# linearSensor.net
KiCad netlist of a schematic drawn in EAGLE
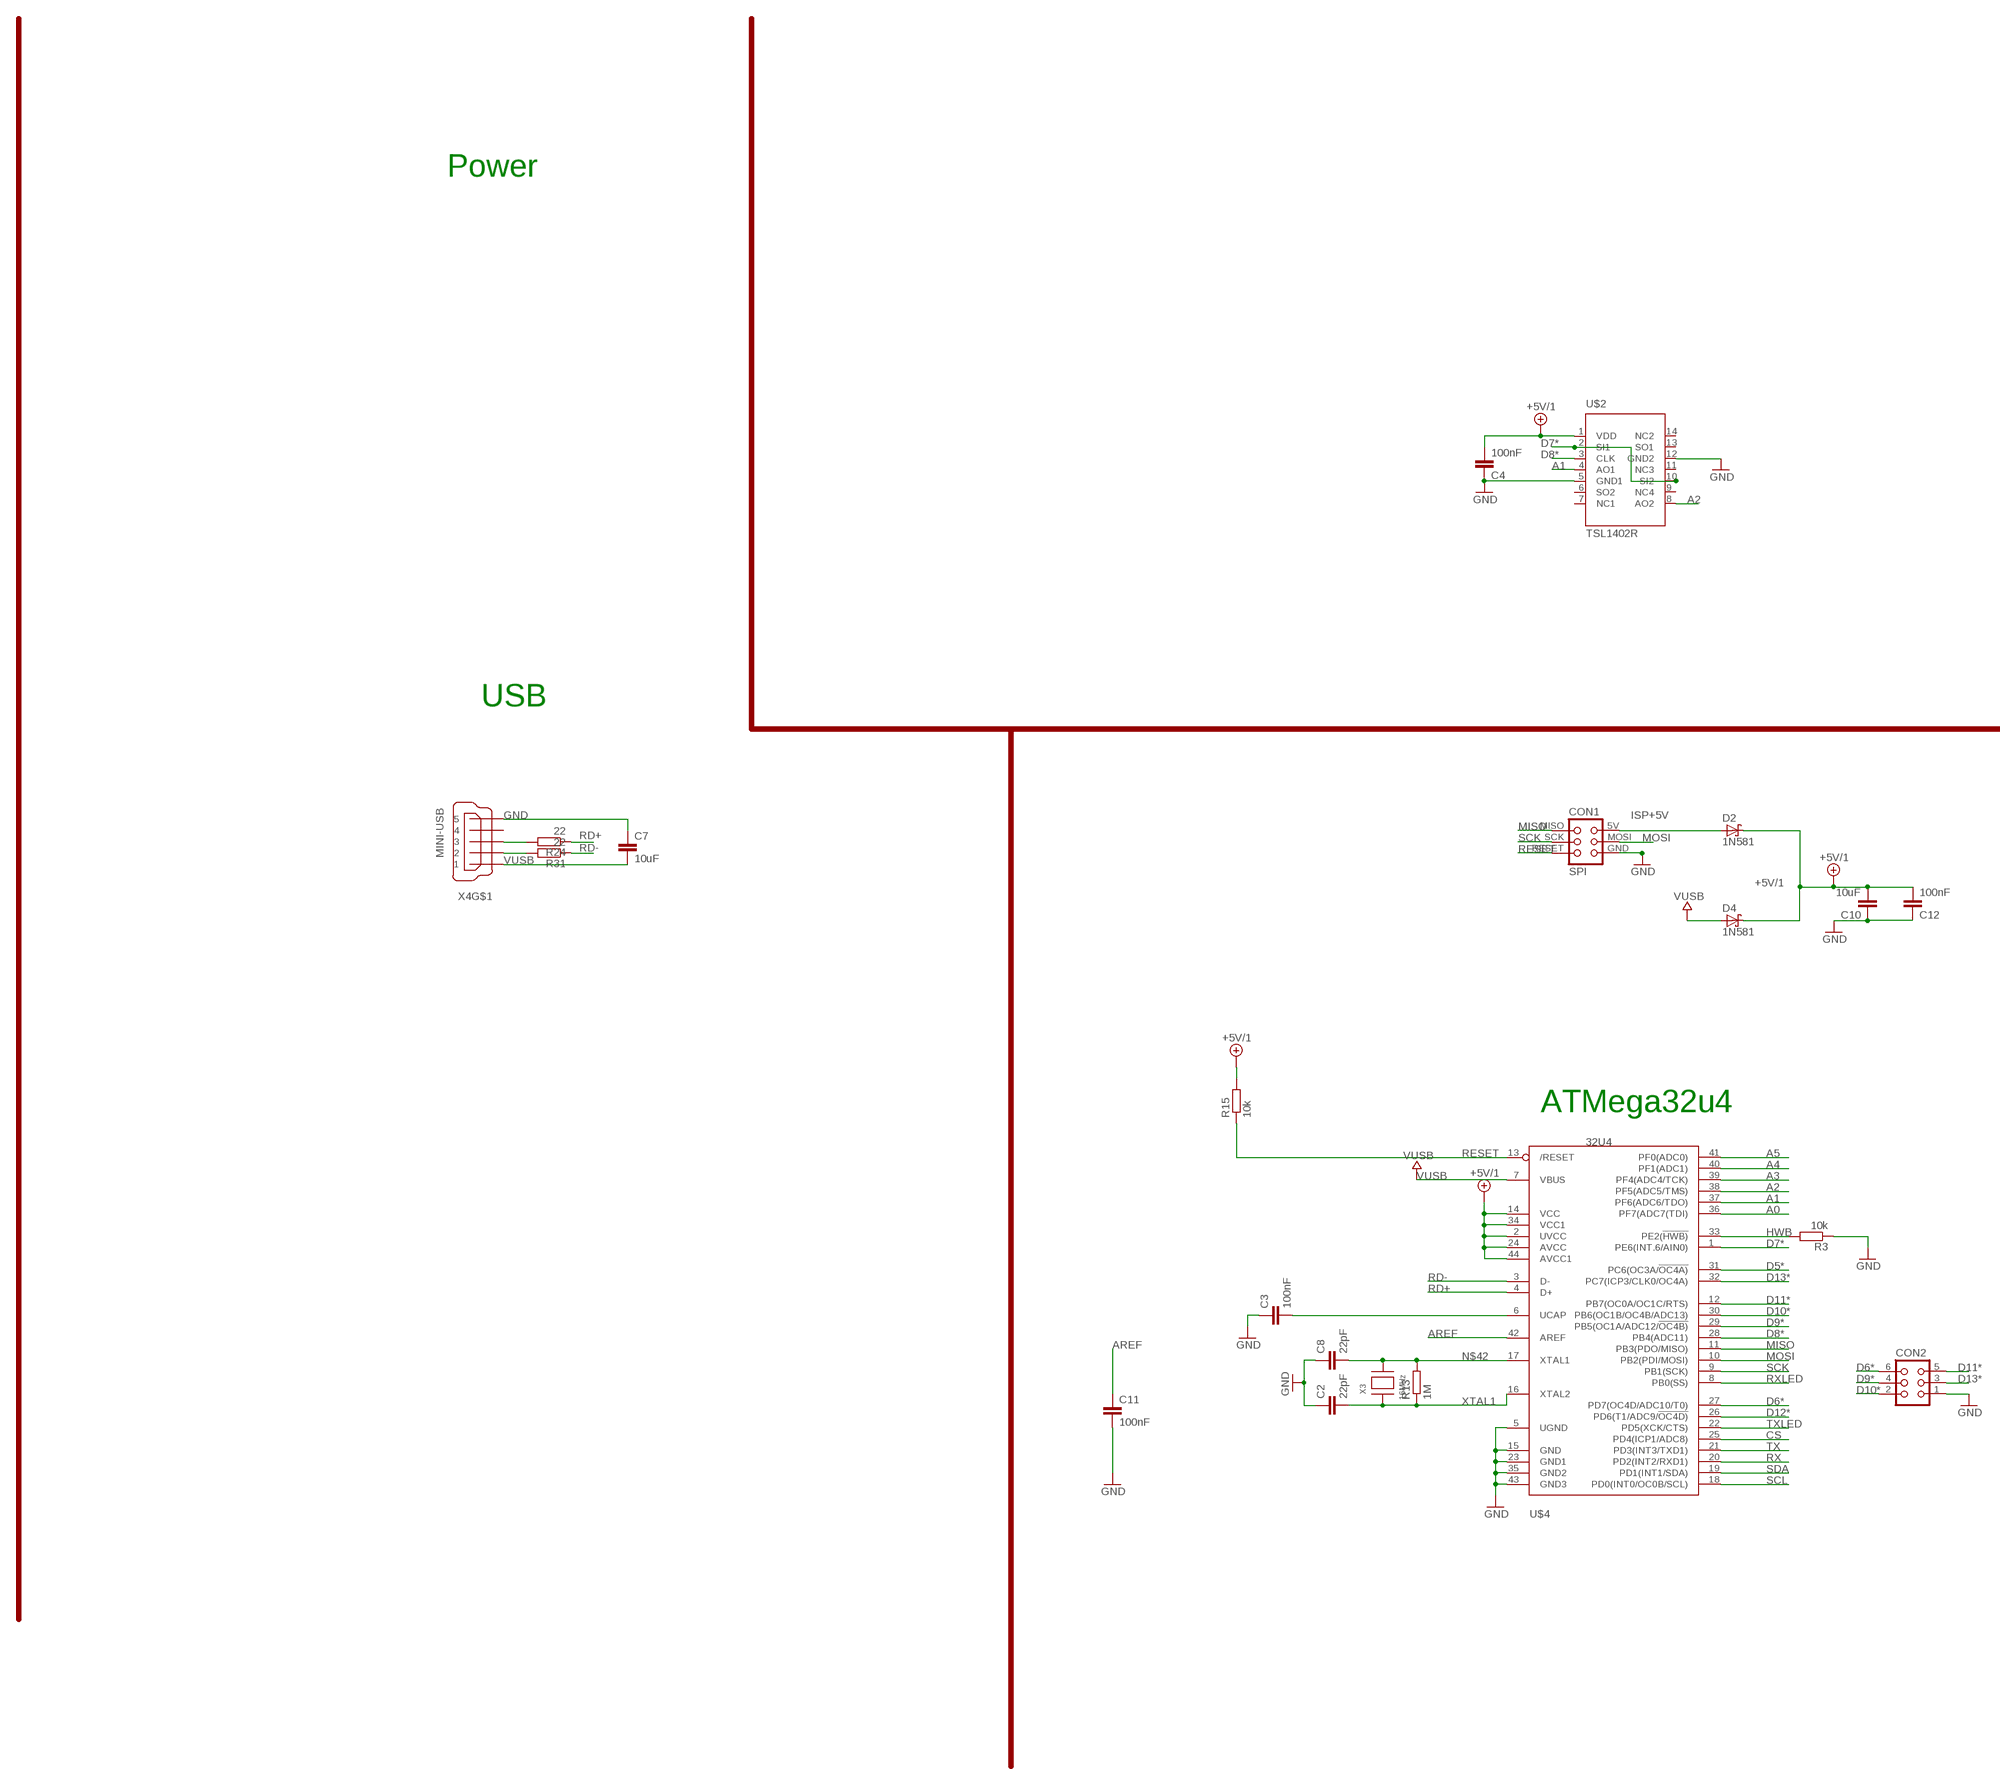
[diagram p0: schematic, sheet 1, part 1 of 2]
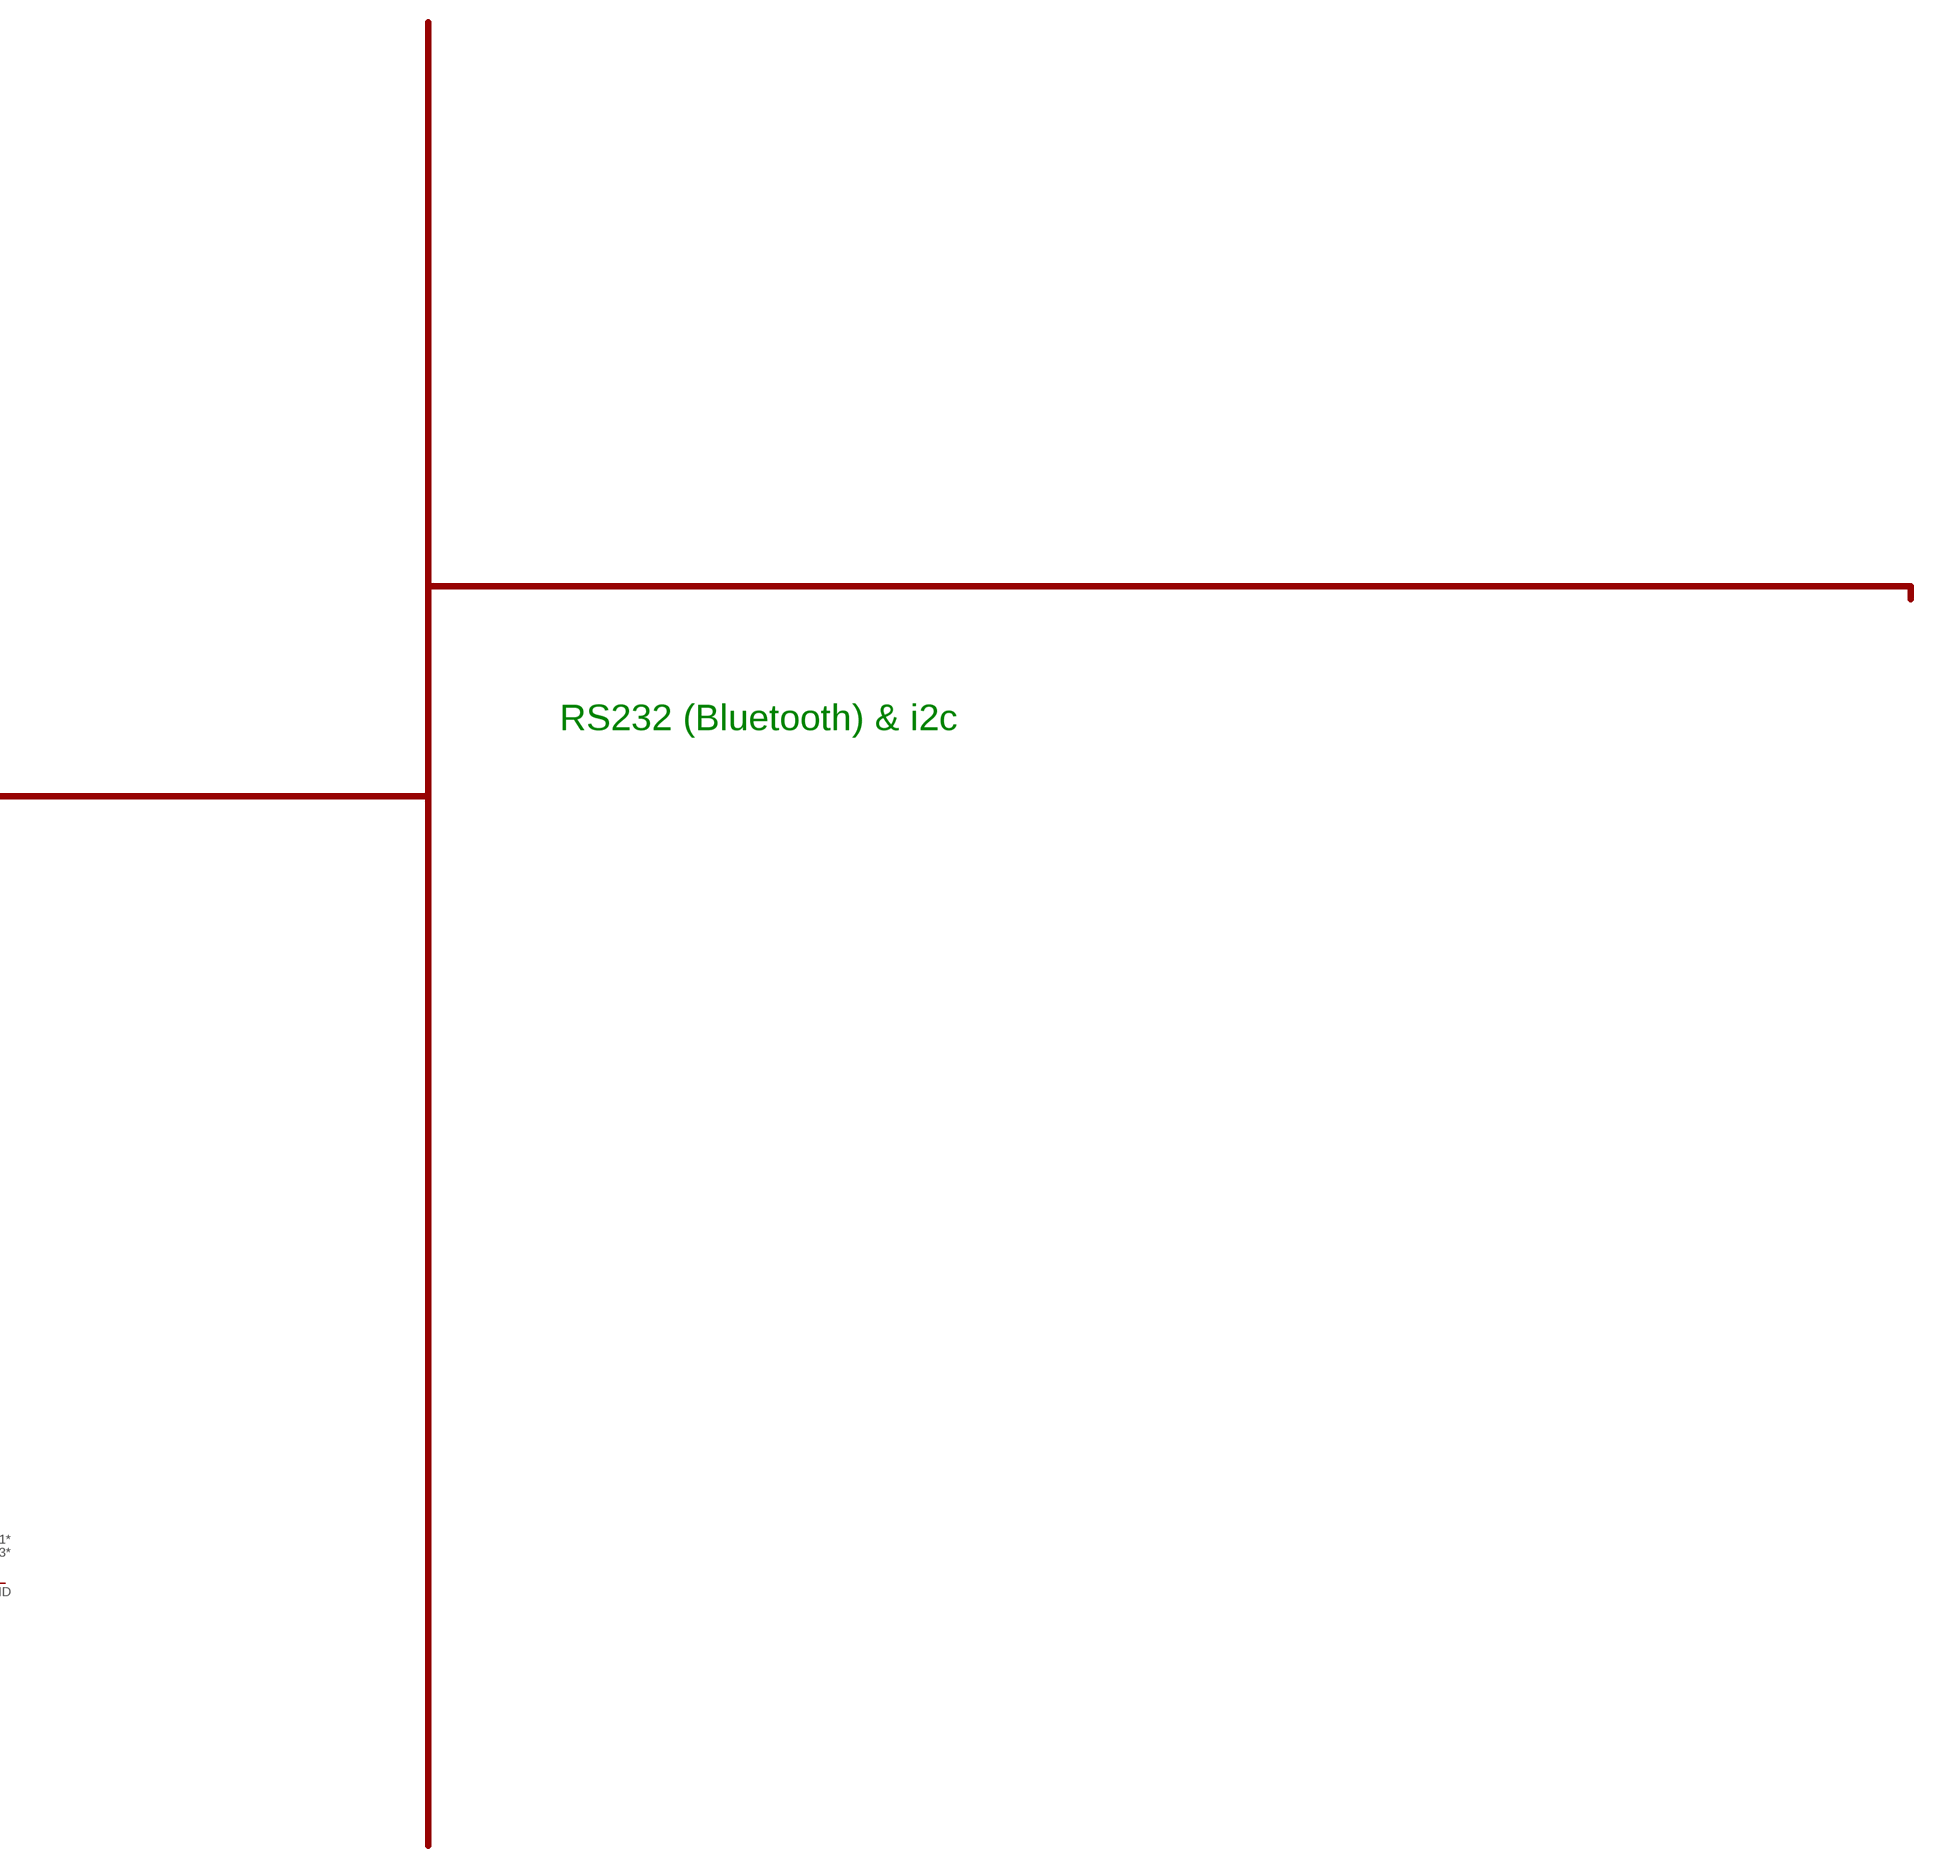
[diagram p1: schematic, sheet 1, part 2 of 2]

(export (version "E")
  (design (tool "Eeschema 10.0.6"))
  (components
    (comp (ref "C2")
      (value "22pF")
      (footprint "eagle-import:C1206")
      (libsource (lib "eagle-import") (part "C-EUC1206"))
    )
    (comp (ref "C3")
      (value "100nF")
      (footprint "eagle-import:C1206")
      (libsource (lib "eagle-import") (part "C-EUC1206"))
    )
    (comp (ref "C4")
      (value "100nF")
      (footprint "eagle-import:C1206")
      (libsource (lib "eagle-import") (part "C-EUC1206"))
    )
    (comp (ref "C7")
      (value "10uF")
      (footprint "eagle-import:C1206")
      (libsource (lib "eagle-import") (part "C-EUC1206"))
    )
    (comp (ref "C8")
      (value "22pF")
      (footprint "eagle-import:C1206")
      (libsource (lib "eagle-import") (part "C-EUC1206"))
    )
    (comp (ref "C10")
      (value "10uF")
      (footprint "eagle-import:C1206")
      (libsource (lib "eagle-import") (part "C-EUC1206"))
    )
    (comp (ref "C11")
      (value "100nF")
      (footprint "eagle-import:C1206")
      (libsource (lib "eagle-import") (part "C-EUC1206"))
    )
    (comp (ref "C12")
      (value "100nF")
      (footprint "eagle-import:C1206")
      (libsource (lib "eagle-import") (part "C-EUC1206"))
    )
    (comp (ref "CON1")
      (value "SPI")
      (footprint "eagle-import:TC2030-MCP-NL")
      (libsource (lib "eagle-import") (part "TINYISPT"))
    )
    (comp (ref "CON2")
      (value "CON06")
      (footprint "eagle-import:CON06")
      (libsource (lib "eagle-import") (part "CON06"))
    )
    (comp (ref "D2")
      (value "1N581")
      (footprint "eagle-import:LED-1206")
      (libsource (lib "eagle-import") (part "1N581D1206"))
    )
    (comp (ref "D4")
      (value "1N581")
      (footprint "eagle-import:LED-1206")
      (libsource (lib "eagle-import") (part "1N581D1206"))
    )
    (comp (ref "R3")
      (value "10k")
      (footprint "eagle-import:M0805")
      (libsource (lib "eagle-import") (part "resistor_R-EU_M0805"))
    )
    (comp (ref "R13")
      (value "1M")
      (footprint "eagle-import:R1206")
      (libsource (lib "eagle-import") (part "R-EU_R1206"))
    )
    (comp (ref "R15")
      (value "10k")
      (footprint "eagle-import:M0805")
      (libsource (lib "eagle-import") (part "resistor_R-EU_M0805"))
    )
    (comp (ref "R24")
      (value "22")
      (footprint "eagle-import:M1206")
      (libsource (lib "eagle-import") (part "resistor_R-EU_M1206"))
    )
    (comp (ref "R31")
      (value "22")
      (footprint "eagle-import:M1206")
      (libsource (lib "eagle-import") (part "resistor_R-EU_M1206"))
    )
    (comp (ref "U$2")
      (value "TSL1402R")
      (footprint "eagle-import:DIL14")
      (libsource (lib "eagle-import") (part "TSL1402R"))
    )
    (comp (ref "U$4")
      (value "32U4")
      (footprint "eagle-import:TQFP44")
      (libsource (lib "eagle-import") (part "ATMEGA32U4-AU"))
    )
    (comp (ref "X3")
      (value "16MHz")
      (footprint "eagle-import:NX6035")
      (libsource (lib "eagle-import") (part "XTALNX6035"))
    )
    (comp (ref "X4")
      (value "MINI-USB")
      (footprint "eagle-import:32005-201")
      (libsource (lib "eagle-import") (part "MINI-USB-SCHIELD-32005-201"))
    )
  )
  (nets
    (net (code "1") (name "+5V{slash}1") (class "Default")
      (node (ref "C10") (pin "2") (pinfunction "2_2") (pintype "passive"))
      (node (ref "C12") (pin "2") (pinfunction "2_2") (pintype "passive"))
      (node (ref "C4") (pin "2") (pinfunction "2_2") (pintype "passive"))
      (node (ref "D2") (pin "C") (pinfunction "C_C") (pintype "passive"))
      (node (ref "D4") (pin "C") (pinfunction "C_C") (pintype "passive"))
      (node (ref "R15") (pin "2") (pinfunction "2_2") (pintype "passive"))
      (node (ref "U$2") (pin "1") (pinfunction "VDD_1") (pintype "power_in"))
      (node (ref "U$4") (pin "14") (pinfunction "VCC_14") (pintype "bidirectional"))
      (node (ref "U$4") (pin "2") (pinfunction "UVCC_2") (pintype "bidirectional"))
      (node (ref "U$4") (pin "24") (pinfunction "AVCC_24") (pintype "bidirectional"))
      (node (ref "U$4") (pin "34") (pinfunction "VCC1_34") (pintype "bidirectional"))
      (node (ref "U$4") (pin "44") (pinfunction "AVCC1_44") (pintype "bidirectional"))
    )
    (net (code "2") (name "/A0") (class "Default")
      (node (ref "U$4") (pin "36") (pinfunction "PF7(ADC7(TDI)_36") (pintype "bidirectional"))
    )
    (net (code "3") (name "/A1") (class "Default")
      (node (ref "U$2") (pin "4") (pinfunction "AO1_4") (pintype "output"))
      (node (ref "U$4") (pin "37") (pinfunction "PF6(ADC6/TDO)_37") (pintype "bidirectional"))
    )
    (net (code "4") (name "/A2") (class "Default")
      (node (ref "U$2") (pin "8") (pinfunction "AO2_8") (pintype "output"))
      (node (ref "U$4") (pin "38") (pinfunction "PF5(ADC5/TMS)_38") (pintype "bidirectional"))
    )
    (net (code "5") (name "/A3") (class "Default")
      (node (ref "U$4") (pin "39") (pinfunction "PF4(ADC4/TCK)_39") (pintype "bidirectional"))
    )
    (net (code "6") (name "/A4") (class "Default")
      (node (ref "U$4") (pin "40") (pinfunction "PF1(ADC1)_40") (pintype "bidirectional"))
    )
    (net (code "7") (name "/A5") (class "Default")
      (node (ref "U$4") (pin "41") (pinfunction "PF0(ADC0)_41") (pintype "bidirectional"))
    )
    (net (code "8") (name "/AREF") (class "Default")
      (node (ref "C11") (pin "1") (pinfunction "1_1") (pintype "passive"))
      (node (ref "U$4") (pin "42") (pinfunction "AREF_42") (pintype "bidirectional"))
    )
    (net (code "9") (name "/CS") (class "Default")
      (node (ref "U$4") (pin "25") (pinfunction "PD4(ICP1/ADC8)_25") (pintype "bidirectional"))
    )
    (net (code "10") (name "/D5*") (class "Default")
      (node (ref "U$4") (pin "31") (pinfunction "PC6(OC3A/~{OC4A})_31") (pintype "bidirectional"))
    )
    (net (code "11") (name "/D6*") (class "Default")
      (node (ref "CON2") (pin "6") (pinfunction "6_6") (pintype "passive"))
      (node (ref "U$4") (pin "27") (pinfunction "PD7(OC4D/ADC10/T0)_27") (pintype "bidirectional"))
    )
    (net (code "12") (name "/D7*") (class "Default")
      (node (ref "U$2") (pin "10") (pinfunction "SI2_10") (pintype "input"))
      (node (ref "U$2") (pin "2") (pinfunction "SI1_2") (pintype "input"))
      (node (ref "U$4") (pin "1") (pinfunction "PE6(INT.6/AIN0)_1") (pintype "bidirectional"))
    )
    (net (code "13") (name "/D8*") (class "Default")
      (node (ref "U$2") (pin "3") (pinfunction "CLK_3") (pintype "input"))
      (node (ref "U$4") (pin "28") (pinfunction "PB4(ADC11)_28") (pintype "bidirectional"))
    )
    (net (code "14") (name "/D9*") (class "Default")
      (node (ref "CON2") (pin "4") (pinfunction "4_4") (pintype "passive"))
      (node (ref "U$4") (pin "29") (pinfunction "PB5(OC1A/ADC12/~{OC4B})_29") (pintype "bidirectional"))
    )
    (net (code "15") (name "/D10*") (class "Default")
      (node (ref "CON2") (pin "2") (pinfunction "2_2") (pintype "passive"))
      (node (ref "U$4") (pin "30") (pinfunction "PB6(OC1B/OC4B/ADC13)_30") (pintype "bidirectional"))
    )
    (net (code "16") (name "/D11*") (class "Default")
      (node (ref "CON2") (pin "5") (pinfunction "5_5") (pintype "passive"))
      (node (ref "U$4") (pin "12") (pinfunction "PB7(OC0A/OC1C/RTS)_12") (pintype "bidirectional"))
    )
    (net (code "17") (name "/D12*") (class "Default")
      (node (ref "U$4") (pin "26") (pinfunction "PD6(T1/ADC9/~{OC4D})_26") (pintype "bidirectional"))
    )
    (net (code "18") (name "/D13*") (class "Default")
      (node (ref "CON2") (pin "3") (pinfunction "3_3") (pintype "passive"))
      (node (ref "U$4") (pin "32") (pinfunction "PC7(ICP3/CLK0/OC4A)_32") (pintype "bidirectional"))
    )
    (net (code "19") (name "/HWB") (class "Default")
      (node (ref "R3") (pin "2") (pinfunction "2_2") (pintype "passive"))
      (node (ref "U$4") (pin "33") (pinfunction "PE2(~{HWB})_33") (pintype "bidirectional"))
    )
    (net (code "20") (name "/ISP+5V") (class "Default")
      (node (ref "CON1") (pin "5V") (pinfunction "VCC_5V") (pintype "passive"))
      (node (ref "D2") (pin "A") (pinfunction "A_A") (pintype "passive"))
    )
    (net (code "21") (name "/MISO") (class "Default")
      (node (ref "CON1") (pin "MISO") (pinfunction "MISO_MISO") (pintype "passive"))
      (node (ref "U$4") (pin "11") (pinfunction "PB3(PDO/MISO)_11") (pintype "bidirectional"))
    )
    (net (code "22") (name "/MOSI") (class "Default")
      (node (ref "CON1") (pin "MOSI") (pinfunction "MOSI_MOSI") (pintype "passive"))
      (node (ref "U$4") (pin "10") (pinfunction "PB2(PDI/MOSI)_10") (pintype "bidirectional"))
    )
    (net (code "23") (name "/N$42") (class "Default")
      (node (ref "C8") (pin "2") (pinfunction "2_2") (pintype "passive"))
      (node (ref "R13") (pin "2") (pinfunction "2_2") (pintype "passive"))
      (node (ref "U$4") (pin "17") (pinfunction "XTAL1_17") (pintype "bidirectional"))
      (node (ref "X3") (pin "P$2") (pinfunction "P$2_P$2") (pintype "bidirectional"))
    )
    (net (code "24") (name "/RD+") (class "Default")
      (node (ref "R24") (pin "1") (pinfunction "1_1") (pintype "passive"))
      (node (ref "U$4") (pin "4") (pinfunction "D+_4") (pintype "bidirectional"))
    )
    (net (code "25") (name "/RD-") (class "Default")
      (node (ref "R31") (pin "1") (pinfunction "1_1") (pintype "passive"))
      (node (ref "U$4") (pin "3") (pinfunction "D-_3") (pintype "bidirectional"))
    )
    (net (code "26") (name "/RESET") (class "Default")
      (node (ref "CON1") (pin "RESET") (pinfunction "RESET_RESET") (pintype "passive"))
      (node (ref "R15") (pin "1") (pinfunction "1_1") (pintype "passive"))
      (node (ref "U$4") (pin "13") (pinfunction "/RESET_13") (pintype "bidirectional"))
    )
    (net (code "27") (name "/RX") (class "Default")
      (node (ref "U$4") (pin "20") (pinfunction "PD2(INT2/RXD1)_20") (pintype "bidirectional"))
    )
    (net (code "28") (name "/RXLED") (class "Default")
      (node (ref "U$4") (pin "8") (pinfunction "PB0(SS)_8") (pintype "bidirectional"))
    )
    (net (code "29") (name "/SCK") (class "Default")
      (node (ref "CON1") (pin "SCK") (pinfunction "SCK_SCK") (pintype "passive"))
      (node (ref "U$4") (pin "9") (pinfunction "PB1(SCK)_9") (pintype "bidirectional"))
    )
    (net (code "30") (name "/SCL") (class "Default")
      (node (ref "U$4") (pin "18") (pinfunction "PD0(INT0/OC0B/SCL)_18") (pintype "bidirectional"))
    )
    (net (code "31") (name "/SDA") (class "Default")
      (node (ref "U$4") (pin "19") (pinfunction "PD1(INT1/SDA)_19") (pintype "bidirectional"))
    )
    (net (code "32") (name "/TX") (class "Default")
      (node (ref "U$4") (pin "21") (pinfunction "PD3(INT3/TXD1)_21") (pintype "bidirectional"))
    )
    (net (code "33") (name "/TXLED") (class "Default")
      (node (ref "U$4") (pin "22") (pinfunction "PD5(XCK/CTS)_22") (pintype "bidirectional"))
    )
    (net (code "34") (name "/XTAL1") (class "Default")
      (node (ref "C2") (pin "2") (pinfunction "2_2") (pintype "passive"))
      (node (ref "R13") (pin "1") (pinfunction "1_1") (pintype "passive"))
      (node (ref "U$4") (pin "16") (pinfunction "XTAL2_16") (pintype "bidirectional"))
      (node (ref "X3") (pin "P$1") (pinfunction "P$1_P$1") (pintype "bidirectional"))
    )
    (net (code "35") (name "GND") (class "Default")
      (node (ref "C10") (pin "1") (pinfunction "1_1") (pintype "passive"))
      (node (ref "C11") (pin "2") (pinfunction "2_2") (pintype "passive"))
      (node (ref "C12") (pin "1") (pinfunction "1_1") (pintype "passive"))
      (node (ref "C2") (pin "1") (pinfunction "1_1") (pintype "passive"))
      (node (ref "C3") (pin "1") (pinfunction "1_1") (pintype "passive"))
      (node (ref "C4") (pin "1") (pinfunction "1_1") (pintype "passive"))
      (node (ref "C7") (pin "1") (pinfunction "1_1") (pintype "passive"))
      (node (ref "C8") (pin "1") (pinfunction "1_1") (pintype "passive"))
      (node (ref "CON1") (pin "GND") (pinfunction "GND_GND") (pintype "passive"))
      (node (ref "CON2") (pin "1") (pinfunction "1_1") (pintype "passive"))
      (node (ref "R3") (pin "1") (pinfunction "1_1") (pintype "passive"))
      (node (ref "U$2") (pin "12") (pinfunction "GND2_12") (pintype "power_in"))
      (node (ref "U$2") (pin "5") (pinfunction "GND1_5") (pintype "power_in"))
      (node (ref "U$4") (pin "15") (pinfunction "GND_15") (pintype "bidirectional"))
      (node (ref "U$4") (pin "23") (pinfunction "GND1_23") (pintype "bidirectional"))
      (node (ref "U$4") (pin "35") (pinfunction "GND2_35") (pintype "bidirectional"))
      (node (ref "U$4") (pin "43") (pinfunction "GND3_43") (pintype "bidirectional"))
      (node (ref "U$4") (pin "5") (pinfunction "UGND_5") (pintype "bidirectional"))
      (node (ref "X4") (pin "5") (pinfunction "5_5") (pintype "passive"))
    )
    (net (code "36") (name "Net-(R24-Pad2)") (class "Default")
      (node (ref "R24") (pin "2") (pinfunction "2_2") (pintype "passive"))
      (node (ref "X4") (pin "3") (pinfunction "3_3") (pintype "passive"))
    )
    (net (code "37") (name "Net-(R31-Pad2)") (class "Default")
      (node (ref "R31") (pin "2") (pinfunction "2_2") (pintype "passive"))
      (node (ref "X4") (pin "2") (pinfunction "2_2") (pintype "passive"))
    )
    (net (code "38") (name "Net-(U$4-UCAP)") (class "Default")
      (node (ref "C3") (pin "2") (pinfunction "2_2") (pintype "passive"))
      (node (ref "U$4") (pin "6") (pinfunction "UCAP_6") (pintype "bidirectional"))
    )
    (net (code "39") (name "VUSB") (class "Default")
      (node (ref "C7") (pin "2") (pinfunction "2_2") (pintype "passive"))
      (node (ref "D4") (pin "A") (pinfunction "A_A") (pintype "passive"))
      (node (ref "U$4") (pin "7") (pinfunction "VBUS_7") (pintype "bidirectional"))
      (node (ref "X4") (pin "1") (pinfunction "1_1") (pintype "passive"))
    )
    (net (code "40") (name "unconnected-(U$2-NC1-Pad7)") (class "Default")
      (node (ref "U$2") (pin "7") (pinfunction "NC1_7") (pintype "no_connect"))
    )
    (net (code "41") (name "unconnected-(U$2-NC2-Pad14)") (class "Default")
      (node (ref "U$2") (pin "14") (pinfunction "NC2_14") (pintype "no_connect"))
    )
    (net (code "42") (name "unconnected-(U$2-NC3-Pad11)") (class "Default")
      (node (ref "U$2") (pin "11") (pinfunction "NC3_11") (pintype "no_connect"))
    )
    (net (code "43") (name "unconnected-(U$2-NC4-Pad9)") (class "Default")
      (node (ref "U$2") (pin "9") (pinfunction "NC4_9") (pintype "no_connect"))
    )
    (net (code "44") (name "unconnected-(U$2-SO1-Pad13)") (class "Default")
      (node (ref "U$2") (pin "13") (pinfunction "SO1_13") (pintype "output"))
    )
    (net (code "45") (name "unconnected-(U$2-SO2-Pad6)") (class "Default")
      (node (ref "U$2") (pin "6") (pinfunction "SO2_6") (pintype "output"))
    )
    (net (code "46") (name "unconnected-(X4-Pad4)") (class "Default")
      (node (ref "X4") (pin "4") (pinfunction "4_4") (pintype "passive"))
    )
  )
)
